# Ex_Controller_ExPwr_USB_Host.net
KiCad netlist of a schematic drawn in EAGLE
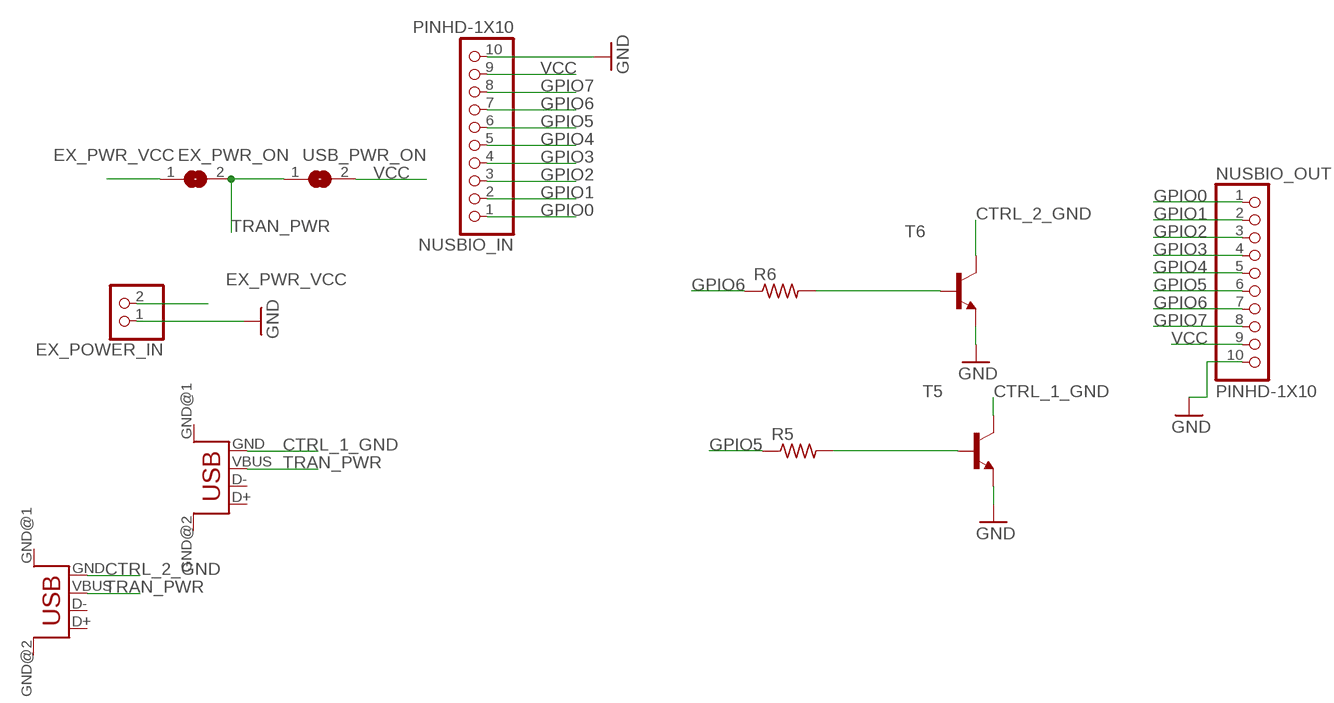
[diagram p0: schematic, sheet 1]

(export (version "E")
  (design (tool "Eeschema 10.0.6"))
  (components
    (comp (ref "EX_DEV_1")
      (value "USB")
      (footprint "eagle-import:USB-FEMALE-A-PTH")
      (libsource (lib "eagle-import") (part "USB"))
    )
    (comp (ref "EX_DEV_2")
      (value "USB")
      (footprint "eagle-import:USB-FEMALE-A-PTH")
      (libsource (lib "eagle-import") (part "USB"))
    )
    (comp (ref "EX_POWER_IN")
      (value "PINHD-1X2")
      (footprint "eagle-import:1X02")
      (libsource (lib "eagle-import") (part "PINHD-1X2"))
    )
    (comp (ref "EX_PWR_ON")
      (value "SOLDERJUMPERREFLOW")
      (footprint "eagle-import:SOLDERJUMPER_REFLOW")
      (libsource (lib "eagle-import") (part "SOLDERJUMPERREFLOW"))
    )
    (comp (ref "NUSBIO_IN")
      (value "PINHD-1X10")
      (footprint "eagle-import:1X10-BIG")
      (libsource (lib "eagle-import") (part "PINHD-1X10"))
    )
    (comp (ref "NUSBIO_OUT")
      (value "PINHD-1X10")
      (footprint "eagle-import:1X10-BIG")
      (libsource (lib "eagle-import") (part "PINHD-1X10"))
    )
    (comp (ref "R5")
      (value "R-US_R0805")
      (footprint "eagle-import:R0805")
      (libsource (lib "eagle-import") (part "R-US_R0805"))
    )
    (comp (ref "R6")
      (value "R-US_R0805")
      (footprint "eagle-import:R0805")
      (libsource (lib "eagle-import") (part "R-US_R0805"))
    )
    (comp (ref "T5")
      (value "MMBT3904LT1-NPN-SOT23-BEC")
      (footprint "eagle-import:SOT23-BEC")
      (libsource (lib "eagle-import") (part "-NPN-SOT23-BECMMBT3904LT1"))
    )
    (comp (ref "T6")
      (value "MMBT3904LT1-NPN-SOT23-BEC")
      (footprint "eagle-import:SOT23-BEC")
      (libsource (lib "eagle-import") (part "-NPN-SOT23-BECMMBT3904LT1"))
    )
    (comp (ref "USB_PWR_ON")
      (value "SOLDERJUMPERREFLOW")
      (footprint "eagle-import:SOLDERJUMPER_REFLOW")
      (libsource (lib "eagle-import") (part "SOLDERJUMPERREFLOW"))
    )
  )
  (nets
    (net (code "1") (name "/CTRL_1_GND") (class "Default")
      (node (ref "EX_DEV_1") (pin "GND") (pinfunction "GND_GND") (pintype "bidirectional"))
      (node (ref "T5") (pin "C") (pinfunction "C_C") (pintype "passive"))
    )
    (net (code "2") (name "/CTRL_2_GND") (class "Default")
      (node (ref "EX_DEV_2") (pin "GND") (pinfunction "GND_GND") (pintype "bidirectional"))
      (node (ref "T6") (pin "C") (pinfunction "C_C") (pintype "passive"))
    )
    (net (code "3") (name "/EX_PWR_VCC") (class "Default")
      (node (ref "EX_POWER_IN") (pin "2") (pinfunction "2_2") (pintype "passive"))
      (node (ref "EX_PWR_ON") (pin "1") (pinfunction "1_1") (pintype "passive"))
    )
    (net (code "4") (name "/GPIO0") (class "Default")
      (node (ref "NUSBIO_IN") (pin "1") (pinfunction "1_1") (pintype "passive"))
      (node (ref "NUSBIO_OUT") (pin "1") (pinfunction "1_1") (pintype "passive"))
    )
    (net (code "5") (name "/GPIO1") (class "Default")
      (node (ref "NUSBIO_IN") (pin "2") (pinfunction "2_2") (pintype "passive"))
      (node (ref "NUSBIO_OUT") (pin "2") (pinfunction "2_2") (pintype "passive"))
    )
    (net (code "6") (name "/GPIO2") (class "Default")
      (node (ref "NUSBIO_IN") (pin "3") (pinfunction "3_3") (pintype "passive"))
      (node (ref "NUSBIO_OUT") (pin "3") (pinfunction "3_3") (pintype "passive"))
    )
    (net (code "7") (name "/GPIO3") (class "Default")
      (node (ref "NUSBIO_IN") (pin "4") (pinfunction "4_4") (pintype "passive"))
      (node (ref "NUSBIO_OUT") (pin "4") (pinfunction "4_4") (pintype "passive"))
    )
    (net (code "8") (name "/GPIO4") (class "Default")
      (node (ref "NUSBIO_IN") (pin "5") (pinfunction "5_5") (pintype "passive"))
      (node (ref "NUSBIO_OUT") (pin "5") (pinfunction "5_5") (pintype "passive"))
    )
    (net (code "9") (name "/GPIO5") (class "Default")
      (node (ref "NUSBIO_IN") (pin "6") (pinfunction "6_6") (pintype "passive"))
      (node (ref "NUSBIO_OUT") (pin "6") (pinfunction "6_6") (pintype "passive"))
      (node (ref "R5") (pin "1") (pinfunction "1_1") (pintype "passive"))
    )
    (net (code "10") (name "/GPIO6") (class "Default")
      (node (ref "NUSBIO_IN") (pin "7") (pinfunction "7_7") (pintype "passive"))
      (node (ref "NUSBIO_OUT") (pin "7") (pinfunction "7_7") (pintype "passive"))
      (node (ref "R6") (pin "1") (pinfunction "1_1") (pintype "passive"))
    )
    (net (code "11") (name "/GPIO7") (class "Default")
      (node (ref "NUSBIO_IN") (pin "8") (pinfunction "8_8") (pintype "passive"))
      (node (ref "NUSBIO_OUT") (pin "8") (pinfunction "8_8") (pintype "passive"))
    )
    (net (code "12") (name "/TRAN_PWR") (class "Default")
      (node (ref "EX_DEV_1") (pin "VBUS") (pinfunction "VBUS_VBUS") (pintype "bidirectional"))
      (node (ref "EX_DEV_2") (pin "VBUS") (pinfunction "VBUS_VBUS") (pintype "bidirectional"))
      (node (ref "EX_PWR_ON") (pin "2") (pinfunction "2_2") (pintype "passive"))
      (node (ref "USB_PWR_ON") (pin "1") (pinfunction "1_1") (pintype "passive"))
    )
    (net (code "13") (name "/VCC") (class "Default")
      (node (ref "NUSBIO_IN") (pin "9") (pinfunction "9_9") (pintype "passive"))
      (node (ref "NUSBIO_OUT") (pin "9") (pinfunction "9_9") (pintype "passive"))
      (node (ref "USB_PWR_ON") (pin "2") (pinfunction "2_2") (pintype "passive"))
    )
    (net (code "14") (name "GND") (class "Default")
      (node (ref "EX_POWER_IN") (pin "1") (pinfunction "1_1") (pintype "passive"))
      (node (ref "NUSBIO_IN") (pin "10") (pinfunction "10_10") (pintype "passive"))
      (node (ref "NUSBIO_OUT") (pin "10") (pinfunction "10_10") (pintype "passive"))
      (node (ref "T5") (pin "E") (pinfunction "E_E") (pintype "passive"))
      (node (ref "T6") (pin "E") (pinfunction "E_E") (pintype "passive"))
    )
    (net (code "15") (name "Net-(R5-Pad2)") (class "Default")
      (node (ref "R5") (pin "2") (pinfunction "2_2") (pintype "passive"))
      (node (ref "T5") (pin "B") (pinfunction "B_B") (pintype "passive"))
    )
    (net (code "16") (name "Net-(R6-Pad2)") (class "Default")
      (node (ref "R6") (pin "2") (pinfunction "2_2") (pintype "passive"))
      (node (ref "T6") (pin "B") (pinfunction "B_B") (pintype "passive"))
    )
    (net (code "17") (name "unconnected-(EX_DEV_1-GND-PadGND@1)") (class "Default")
      (node (ref "EX_DEV_1") (pin "GND@1") (pinfunction "GND_GND@1") (pintype "bidirectional"))
    )
    (net (code "18") (name "unconnected-(EX_DEV_1-GND-PadGND@2)") (class "Default")
      (node (ref "EX_DEV_1") (pin "GND@2") (pinfunction "GND_GND@2") (pintype "bidirectional"))
    )
    (net (code "19") (name "unconnected-(EX_DEV_1-PadD+)") (class "Default")
      (node (ref "EX_DEV_1") (pin "D+") (pinfunction "D+_D+") (pintype "bidirectional"))
    )
    (net (code "20") (name "unconnected-(EX_DEV_1-PadD-)") (class "Default")
      (node (ref "EX_DEV_1") (pin "D-") (pinfunction "D-_D-") (pintype "bidirectional"))
    )
    (net (code "21") (name "unconnected-(EX_DEV_2-GND-PadGND@1)") (class "Default")
      (node (ref "EX_DEV_2") (pin "GND@1") (pinfunction "GND_GND@1") (pintype "bidirectional"))
    )
    (net (code "22") (name "unconnected-(EX_DEV_2-GND-PadGND@2)") (class "Default")
      (node (ref "EX_DEV_2") (pin "GND@2") (pinfunction "GND_GND@2") (pintype "bidirectional"))
    )
    (net (code "23") (name "unconnected-(EX_DEV_2-PadD+)") (class "Default")
      (node (ref "EX_DEV_2") (pin "D+") (pinfunction "D+_D+") (pintype "bidirectional"))
    )
    (net (code "24") (name "unconnected-(EX_DEV_2-PadD-)") (class "Default")
      (node (ref "EX_DEV_2") (pin "D-") (pinfunction "D-_D-") (pintype "bidirectional"))
    )
  )
)
